# Teensylu2-0_9.net
KiCad netlist of a schematic drawn in EAGLE
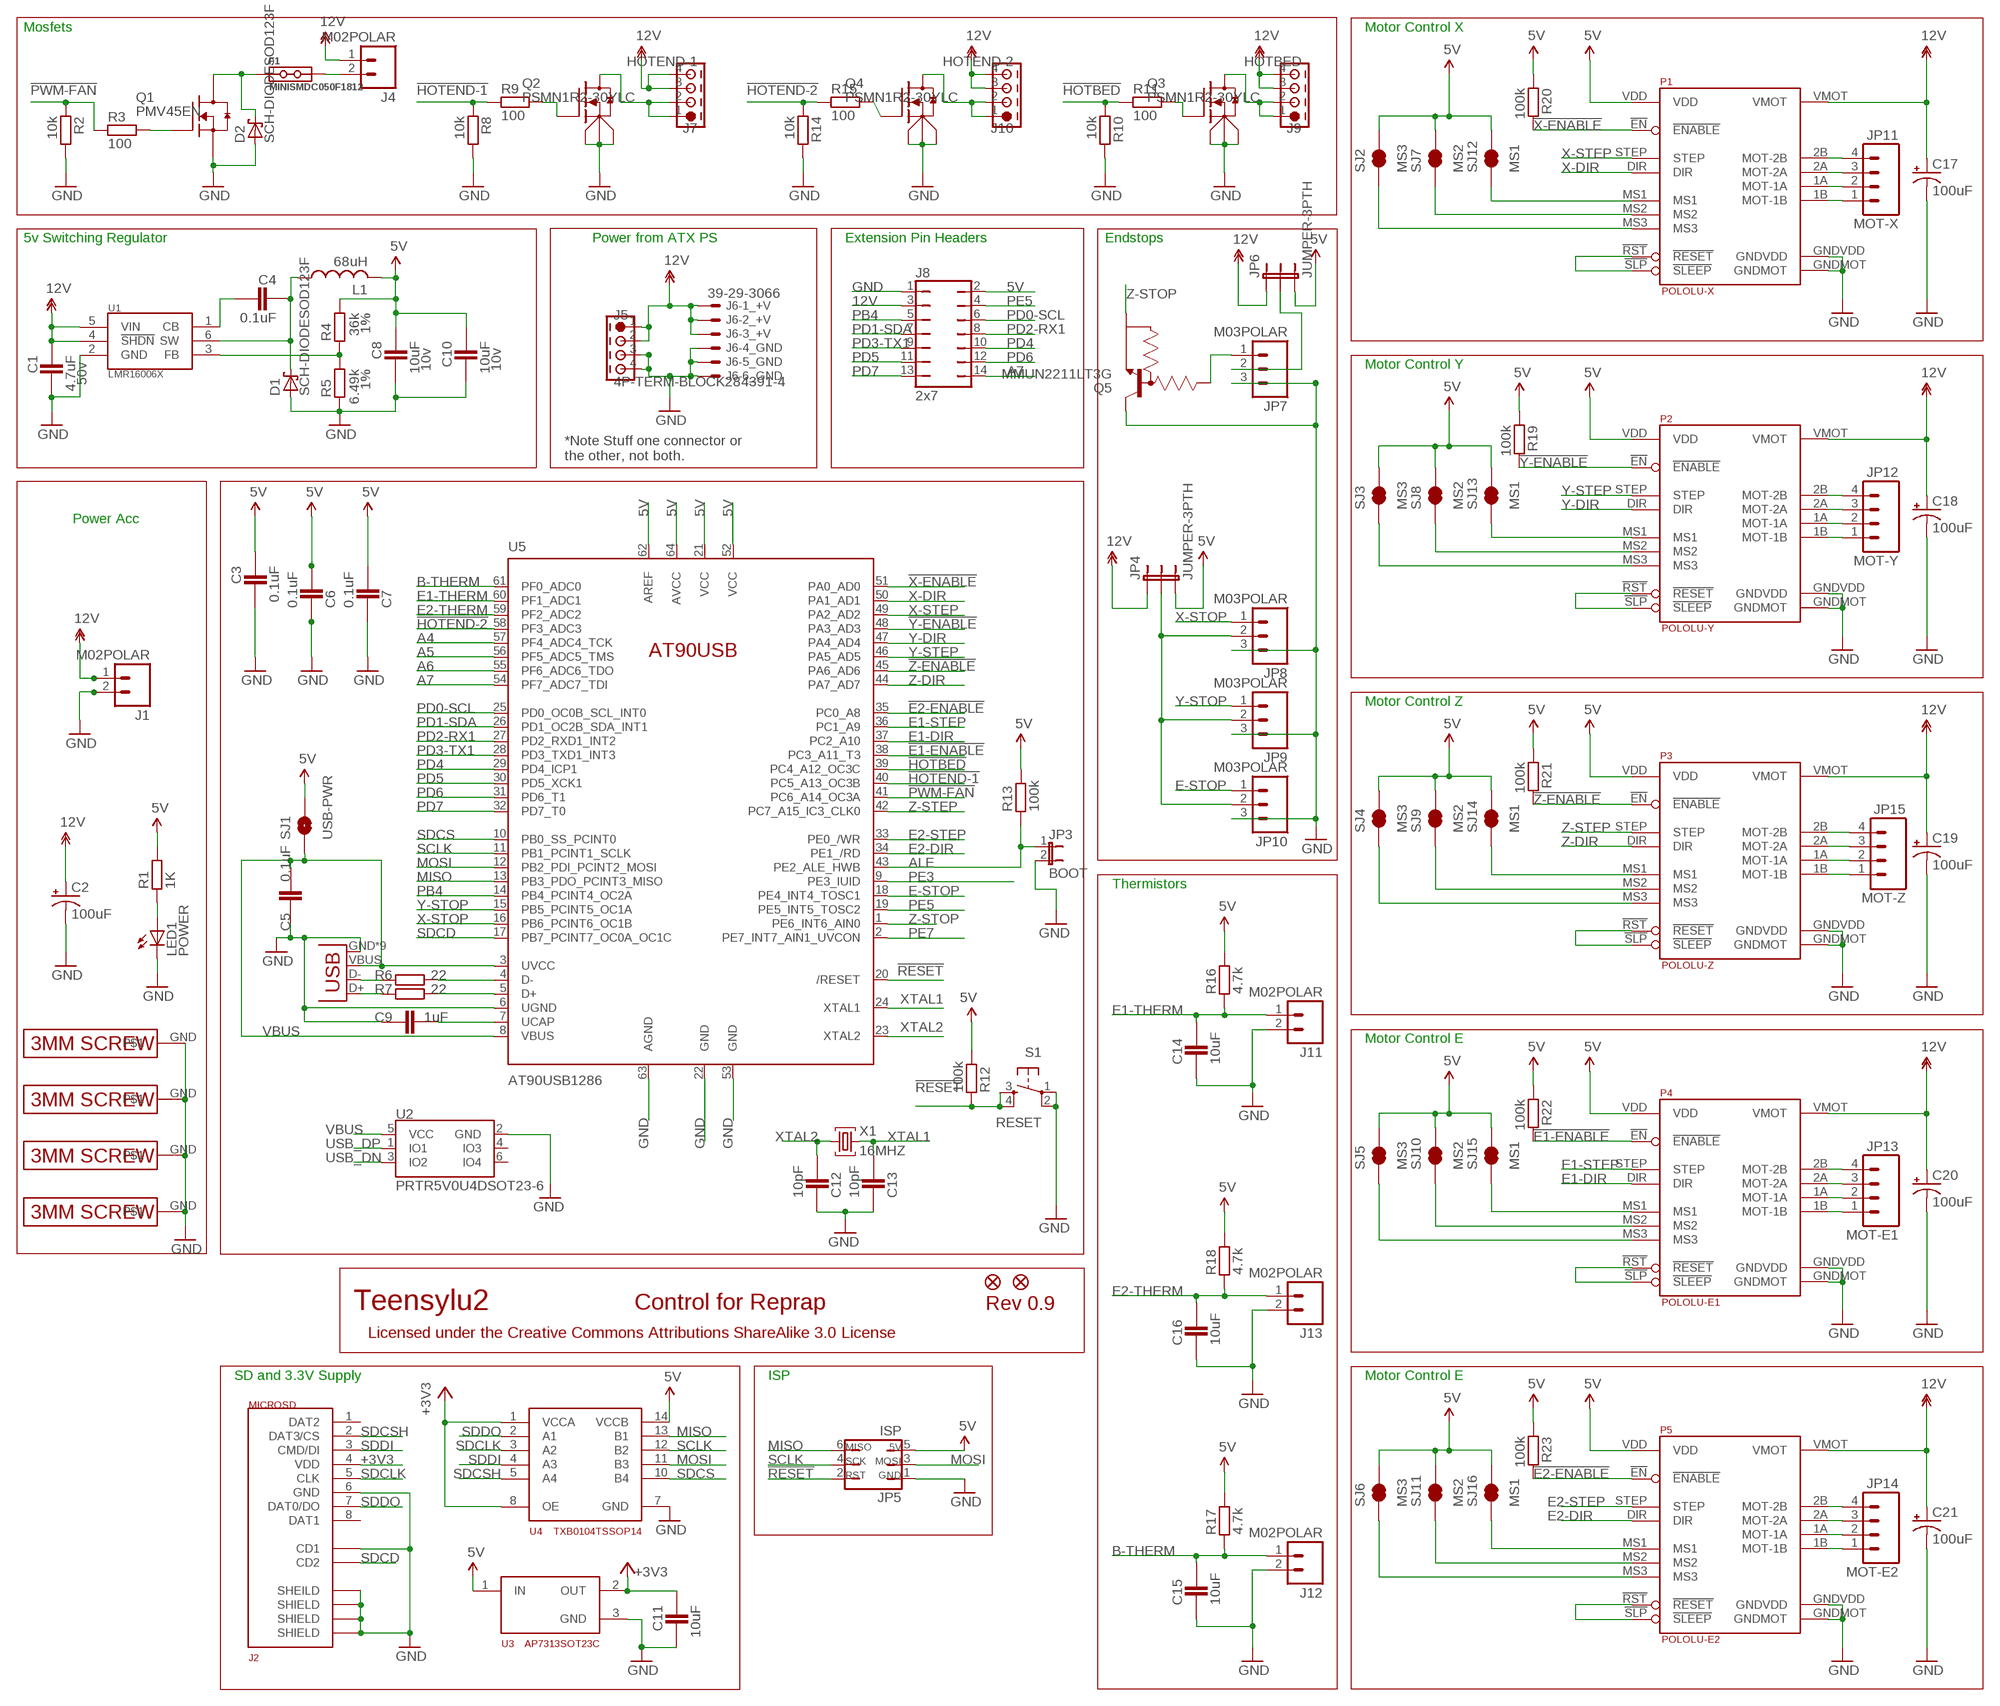
[diagram p0: schematic, sheet 1]

(export (version "E")
  (design (tool "Eeschema 10.0.6"))
  (components
    (comp (ref "C1")
      (value "4.7uF")
      (footprint "eagle-import:CAPC3215X168N")
      (fields
        (field (name "MANUFACTURER") "Yaiyo Yuden")
        (field (name "MANUFACTURER_PART_NUMBER") "UMK316AB7475KL-T")
        (field (name "TOLERANCE") "10%")
        (field (name "VDC") "50v")
      )
      (libsource (lib "eagle-import") (part "CAPACITOR_1206"))
    )
    (comp (ref "C2")
      (value "100uF")
      (footprint "eagle-import:PANASONIC_D")
      (fields
        (field (name "MANUFACTURER") "Panasonic")
        (field (name "MANUFACTURER_PART_NUMBER") "EEE-FTH101XAP")
        (field (name "TOLERANCE") "20%")
      )
      (libsource (lib "eagle-import") (part "CPOL-USD"))
    )
    (comp (ref "C3")
      (value "0.1uF")
      (footprint "eagle-import:CAPC1608X92N")
      (fields
        (field (name "MANUFACTURER") "Murata")
        (field (name "MANUFACTURER_PART_NUMBER") "GRM188R71C104KA01D")
        (field (name "TOLERANCE") "10%")
      )
      (libsource (lib "eagle-import") (part "CAPACITOR_0603"))
    )
    (comp (ref "C4")
      (value "0.1uF")
      (footprint "eagle-import:CAPC1608X92N")
      (fields
        (field (name "MANUFACTURER") "Samsung")
        (field (name "MANUFACTURER_PART_NUMBER") "CL10B104KB8NNNC")
        (field (name "TOLERANCE") "10%")
      )
      (libsource (lib "eagle-import") (part "CAPACITOR_0603"))
    )
    (comp (ref "C5")
      (value "0.1uF")
      (footprint "eagle-import:CAPC1608X92N")
      (fields
        (field (name "MANUFACTURER") "Murata")
        (field (name "MANUFACTURER_PART_NUMBER") "GRM188R71C104KA01D")
        (field (name "TOLERANCE") "10%")
      )
      (libsource (lib "eagle-import") (part "CAPACITOR_0603"))
    )
    (comp (ref "C6")
      (value "0.1uF")
      (footprint "eagle-import:CAPC1608X92N")
      (fields
        (field (name "MANUFACTURER") "Murata")
        (field (name "MANUFACTURER_PART_NUMBER") "GRM188R71C104KA01D")
        (field (name "TOLERANCE") "10%")
      )
      (libsource (lib "eagle-import") (part "CAPACITOR_0603"))
    )
    (comp (ref "C7")
      (value "0.1uF")
      (footprint "eagle-import:CAPC1608X92N")
      (fields
        (field (name "MANUFACTURER") "Murata")
        (field (name "MANUFACTURER_PART_NUMBER") "GRM188R71C104KA01D")
        (field (name "TOLERANCE") "10%")
      )
      (libsource (lib "eagle-import") (part "CAPACITOR_0603"))
    )
    (comp (ref "C8")
      (value "10uF")
      (footprint "eagle-import:CAPC2012X145AN")
      (fields
        (field (name "MANUFACTURER") "Murata")
        (field (name "MANUFACTURER_PART_NUMBER") "GRM21BR71A106KE51L")
        (field (name "TOLERANCE") "10%")
        (field (name "VDC") "10v")
      )
      (libsource (lib "eagle-import") (part "CAPACITOR_0805"))
    )
    (comp (ref "C9")
      (value "1uF")
      (footprint "eagle-import:CAPC1608X92N")
      (fields
        (field (name "MANUFACTURER") "Samsung")
        (field (name "MANUFACTURER_PART_NUMBER") "CL10A105MO8NNNC")
        (field (name "TOLERANCE") "20%")
      )
      (libsource (lib "eagle-import") (part "CAPACITOR_0603"))
    )
    (comp (ref "C10")
      (value "10uF")
      (footprint "eagle-import:CAPC2012X145AN")
      (fields
        (field (name "MANUFACTURER") "Murata")
        (field (name "MANUFACTURER_PART_NUMBER") "GRM21BR71A106KE51L")
        (field (name "TOLERANCE") "10%")
        (field (name "VDC") "10v")
      )
      (libsource (lib "eagle-import") (part "CAPACITOR_0805"))
    )
    (comp (ref "C11")
      (value "10uF")
      (footprint "eagle-import:CAPC1608X92N")
      (fields
        (field (name "MANUFACTURER") "Murata")
        (field (name "MANUFACTURER_PART_NUMBER") "GRM188R61C106MA73D")
        (field (name "TOLERANCE") "20%")
      )
      (libsource (lib "eagle-import") (part "CAPACITOR_0603"))
    )
    (comp (ref "C12")
      (value "10pF")
      (footprint "eagle-import:CAPC1608X92N")
      (fields
        (field (name "MANUFACTURER") "Samsung")
        (field (name "MANUFACTURER_PART_NUMBER") "CL10C100JB8NCNC")
        (field (name "TOLERANCE") "5%")
      )
      (libsource (lib "eagle-import") (part "CAPACITOR_0603"))
    )
    (comp (ref "C13")
      (value "10pF")
      (footprint "eagle-import:CAPC1608X92N")
      (fields
        (field (name "MANUFACTURER") "Samsung")
        (field (name "MANUFACTURER_PART_NUMBER") "CL10C100JB8NCNC")
        (field (name "TOLERANCE") "5%")
      )
      (libsource (lib "eagle-import") (part "CAPACITOR_0603"))
    )
    (comp (ref "C14")
      (value "10uF")
      (footprint "eagle-import:CAPC1608X92N")
      (fields
        (field (name "MANUFACTURER") "Murata")
        (field (name "MANUFACTURER_PART_NUMBER") "GRM188R61C106MA73D")
        (field (name "TOLERANCE") "20%")
      )
      (libsource (lib "eagle-import") (part "CAPACITOR_0603"))
    )
    (comp (ref "C15")
      (value "10uF")
      (footprint "eagle-import:CAPC1608X92N")
      (fields
        (field (name "MANUFACTURER") "Murata")
        (field (name "MANUFACTURER_PART_NUMBER") "GRM188R61C106MA73D")
        (field (name "TOLERANCE") "20%")
      )
      (libsource (lib "eagle-import") (part "CAPACITOR_0603"))
    )
    (comp (ref "C16")
      (value "10uF")
      (footprint "eagle-import:CAPC1608X92N")
      (fields
        (field (name "MANUFACTURER") "Murata")
        (field (name "MANUFACTURER_PART_NUMBER") "GRM188R61C106MA73D")
        (field (name "TOLERANCE") "20%")
      )
      (libsource (lib "eagle-import") (part "CAPACITOR_0603"))
    )
    (comp (ref "C17")
      (value "100uF")
      (footprint "eagle-import:PANASONIC_D")
      (fields
        (field (name "MANUFACTURER") "Panasonic")
        (field (name "MANUFACTURER_PART_NUMBER") "EEE-FTH101XAP")
        (field (name "TOLERANCE") "20%")
      )
      (libsource (lib "eagle-import") (part "CPOL-USD"))
    )
    (comp (ref "C18")
      (value "100uF")
      (footprint "eagle-import:PANASONIC_D")
      (fields
        (field (name "MANUFACTURER") "Panasonic")
        (field (name "MANUFACTURER_PART_NUMBER") "EEE-FTH101XAP")
        (field (name "TOLERANCE") "20%")
      )
      (libsource (lib "eagle-import") (part "CPOL-USD"))
    )
    (comp (ref "C19")
      (value "100uF")
      (footprint "eagle-import:PANASONIC_D")
      (fields
        (field (name "MANUFACTURER") "Panasonic")
        (field (name "MANUFACTURER_PART_NUMBER") "EEE-FTH101XAP")
        (field (name "TOLERANCE") "20%")
      )
      (libsource (lib "eagle-import") (part "CPOL-USD"))
    )
    (comp (ref "C20")
      (value "100uF")
      (footprint "eagle-import:PANASONIC_D")
      (fields
        (field (name "MANUFACTURER") "Panasonic")
        (field (name "MANUFACTURER_PART_NUMBER") "EEE-FTH101XAP")
        (field (name "TOLERANCE") "20%")
      )
      (libsource (lib "eagle-import") (part "CPOL-USD"))
    )
    (comp (ref "C21")
      (value "100uF")
      (footprint "eagle-import:PANASONIC_D")
      (fields
        (field (name "MANUFACTURER") "Panasonic")
        (field (name "MANUFACTURER_PART_NUMBER") "EEE-FTH101XAP")
        (field (name "TOLERANCE") "20%")
      )
      (libsource (lib "eagle-import") (part "CPOL-USD"))
    )
    (comp (ref "D1")
      (value "SCH-DIODESOD123F")
      (footprint "eagle-import:SOD123F")
      (fields
        (field (name "MANUFACTURER") "NXP Semiconductors")
        (field (name "MANUFACTURER_PART_NUMBER") "PMEG4010CEH,115")
        (field (name "CURRENT") "1A")
        (field (name "MANUFACTURER_1") "NXP Semiconductors")
        (field (name "MANUFACTURER_PART_NUMBER_1") "PMEG4010CEH,115")
        (field (name "REVERSE_VOLTAGE") "40V")
      )
      (libsource (lib "eagle-import") (part "SCH-DIODESOD123F"))
    )
    (comp (ref "D2")
      (value "SCH-DIODESOD123F")
      (footprint "eagle-import:SOD123F")
      (fields
        (field (name "MANUFACTURER") "NXP Semiconductors")
        (field (name "MANUFACTURER_PART_NUMBER") "PMEG4010CEH,115")
        (field (name "CURRENT") "1A")
        (field (name "MANUFACTURER_1") "NXP Semiconductors")
      )
      (libsource (lib "eagle-import") (part "SCH-DIODESOD123F"))
    )
    (comp (ref "F1")
      (value "MINISMDC050F1812")
      (footprint "eagle-import:MINISMDC")
      (fields
        (field (name "MANUFACTURER") "TE Connectivity")
        (field (name "MANUFACTURER_PART_NUMBER") "MINISMDC050F-2")
      )
      (libsource (lib "eagle-import") (part "MINISMDC050F1812"))
    )
    (comp (ref "J1")
      (value "M02POLAR")
      (footprint "eagle-import:MOLEX-1X2")
      (description "CONN HEADER 2POS .100 VERT TIN")
      (fields (field (name "MANUFACTURER") "Molex") (field (name "MANUFACTURER_PART_NUMBER") "0022272021"))
      (libsource (lib "eagle-import") (part "M02POLAR"))
    )
    (comp (ref "J2")
      (value "MICROSD")
      (footprint "eagle-import:AMPHENOL-MICROSD")
      (description "CONN MICRO SD CARD PUSH-PULL R/A")
      (fields
        (field (name "MANUFACTURER") "Amphenol")
        (field (name "MANUFACTURER_PART_NUMBER") "114-00841-68")
      )
      (libsource (lib "eagle-import") (part "MICROSD"))
    )
    (comp (ref "J3")
      (value "USB-MICRO-PTH")
      (footprint "eagle-import:USB-MICROB-PTH")
      (fields (field (name "MANUFACTURER") "FCI") (field (name "MANUFACTURER_PART_NUMBER") "10118194-0001LF"))
      (libsource (lib "eagle-import") (part "USB-MICRO-PTH"))
    )
    (comp (ref "J4")
      (value "M02POLAR")
      (footprint "eagle-import:MOLEX-1X2")
      (description "CONN HEADER 2POS .100 VERT TIN")
      (fields (field (name "MANUFACTURER") "Molex") (field (name "MANUFACTURER_PART_NUMBER") "0022272021"))
      (libsource (lib "eagle-import") (part "M02POLAR"))
    )
    (comp (ref "J5")
      (value "4P-TERM-BLOCK284391-4")
      (footprint "eagle-import:284391-4")
      (fields
        (field (name "MANUFACTURER") "TE Connectivity")
        (field (name "MANUFACTURER_PART_NUMBER") "284391-4")
      )
      (libsource (lib "eagle-import") (part "4P-TERM-BLOCK284391-4"))
    )
    (comp (ref "J6")
      (value "39-29-3066")
      (footprint "eagle-import:39-29-3066")
      (fields (field (name "MANUFACTURER") "Molex") (field (name "MANUFACTURER_PART_NUMBER") "0039293066"))
      (libsource (lib "eagle-import") (part "39-29-3066"))
    )
    (comp (ref "J7")
      (value "HOTEND-1")
      (footprint "eagle-import:282834-4")
      (fields
        (field (name "MANUFACTURER") "TE Connectivity")
        (field (name "MANUFACTURER_PART_NUMBER") "282834-4")
      )
      (libsource (lib "eagle-import") (part "4P-TERM-BLOCK282834-4"))
    )
    (comp (ref "J8")
      (value "2x7")
      (footprint "eagle-import:JP7Q")
      (description "DIL VERTICAL PC TAIL PIN HEADER")
      (fields (field (name "MANUFACTURER") "Harwin") (field (name "MANUFACTURER_PART_NUMBER") "M20-9980746"))
      (libsource (lib "eagle-import") (part "JP7Q"))
    )
    (comp (ref "J9")
      (value "HOTBED")
      (footprint "eagle-import:284391-4")
      (fields
        (field (name "MANUFACTURER") "TE Connectivity")
        (field (name "MANUFACTURER_PART_NUMBER") "284391-4")
      )
      (libsource (lib "eagle-import") (part "4P-TERM-BLOCK284391-4"))
    )
    (comp (ref "J10")
      (value "HOTEND-2")
      (footprint "eagle-import:282834-4")
      (fields
        (field (name "MANUFACTURER") "TE Connectivity")
        (field (name "MANUFACTURER_PART_NUMBER") "282834-4")
      )
      (libsource (lib "eagle-import") (part "4P-TERM-BLOCK282834-4"))
    )
    (comp (ref "J11")
      (value "M02POLAR")
      (footprint "eagle-import:MOLEX-1X2")
      (description "CONN HEADER 2POS .100 VERT TIN")
      (fields (field (name "MANUFACTURER") "Molex") (field (name "MANUFACTURER_PART_NUMBER") "0022272021"))
      (libsource (lib "eagle-import") (part "M02POLAR"))
    )
    (comp (ref "J12")
      (value "M02POLAR")
      (footprint "eagle-import:MOLEX-1X2")
      (description "CONN HEADER 2POS .100 VERT TIN")
      (fields (field (name "MANUFACTURER") "Molex") (field (name "MANUFACTURER_PART_NUMBER") "0022272021"))
      (libsource (lib "eagle-import") (part "M02POLAR"))
    )
    (comp (ref "J13")
      (value "M02POLAR")
      (footprint "eagle-import:MOLEX-1X2")
      (description "CONN HEADER 2POS .100 VERT TIN")
      (fields (field (name "MANUFACTURER") "Molex") (field (name "MANUFACTURER_PART_NUMBER") "0022272021"))
      (libsource (lib "eagle-import") (part "M02POLAR"))
    )
    (comp (ref "JP1")
      (value "FIDUCIAL1X2.5")
      (footprint "eagle-import:FIDUCIAL-1X2.5")
      (libsource (lib "eagle-import") (part "FIDUCIAL1X2.5"))
    )
    (comp (ref "JP2")
      (value "FIDUCIAL1X2.5")
      (footprint "eagle-import:FIDUCIAL-1X2.5")
      (libsource (lib "eagle-import") (part "FIDUCIAL1X2.5"))
    )
    (comp (ref "JP3")
      (value "BOOT")
      (footprint "eagle-import:1X02")
      (description "SIL VERTICAL PC TAIL PIN HEADER")
      (fields (field (name "MANUFACTURER") "Harwin") (field (name "MANUFACTURER_PART_NUMBER") "M20-9990246"))
      (libsource (lib "eagle-import") (part "JUMPER-2PTH"))
    )
    (comp (ref "JP4")
      (value "JUMPER-3PTH")
      (footprint "eagle-import:1X03")
      (libsource (lib "eagle-import") (part "JUMPER-3PTH"))
    )
    (comp (ref "JP5")
      (value "ISP")
      (footprint "eagle-import:ISP")
      (libsource (lib "eagle-import") (part "PROGHEADER"))
    )
    (comp (ref "JP6")
      (value "JUMPER-3PTH")
      (footprint "eagle-import:1X03")
      (libsource (lib "eagle-import") (part "JUMPER-3PTH"))
    )
    (comp (ref "JP7")
      (value "M03POLAR")
      (footprint "eagle-import:MOLEX-1X3")
      (description "CONN HEADER 3POS .100 VERT TIN")
      (fields (field (name "MANUFACTURER") "Molex") (field (name "MANUFACTURER_PART_NUMBER") "0022272031"))
      (libsource (lib "eagle-import") (part "M03POLAR"))
    )
    (comp (ref "JP8")
      (value "M03POLAR")
      (footprint "eagle-import:MOLEX-1X3")
      (description "CONN HEADER 3POS .100 VERT TIN")
      (fields (field (name "MANUFACTURER") "Molex") (field (name "MANUFACTURER_PART_NUMBER") "0022272031"))
      (libsource (lib "eagle-import") (part "M03POLAR"))
    )
    (comp (ref "JP9")
      (value "M03POLAR")
      (footprint "eagle-import:MOLEX-1X3")
      (description "CONN HEADER 3POS .100 VERT TIN")
      (fields (field (name "MANUFACTURER") "Molex") (field (name "MANUFACTURER_PART_NUMBER") "0022272031"))
      (libsource (lib "eagle-import") (part "M03POLAR"))
    )
    (comp (ref "JP10")
      (value "M03POLAR")
      (footprint "eagle-import:MOLEX-1X3")
      (description "CONN HEADER 3POS .100 VERT TIN")
      (fields (field (name "MANUFACTURER") "Molex") (field (name "MANUFACTURER_PART_NUMBER") "0022272031"))
      (libsource (lib "eagle-import") (part "M03POLAR"))
    )
    (comp (ref "JP11")
      (value "MOT-X")
      (footprint "eagle-import:MOLEX-1X4")
      (fields (field (name "MANUFACTURER") "Molex") (field (name "MANUFACTURER_PART_NUMBER") "0022272041"))
      (libsource (lib "eagle-import") (part "M04POLAR"))
    )
    (comp (ref "JP12")
      (value "MOT-Y")
      (footprint "eagle-import:MOLEX-1X4")
      (fields (field (name "MANUFACTURER") "Molex") (field (name "MANUFACTURER_PART_NUMBER") "0022272041"))
      (libsource (lib "eagle-import") (part "M04POLAR"))
    )
    (comp (ref "JP13")
      (value "MOT-E1")
      (footprint "eagle-import:MOLEX-1X4")
      (fields (field (name "MANUFACTURER") "Molex") (field (name "MANUFACTURER_PART_NUMBER") "0022272041"))
      (libsource (lib "eagle-import") (part "M04POLAR"))
    )
    (comp (ref "JP14")
      (value "MOT-E2")
      (footprint "eagle-import:MOLEX-1X4")
      (fields (field (name "MANUFACTURER") "Molex") (field (name "MANUFACTURER_PART_NUMBER") "0022272041"))
      (libsource (lib "eagle-import") (part "M04POLAR"))
    )
    (comp (ref "JP15")
      (value "MOT-Z")
      (footprint "eagle-import:MOLEX-1X4")
      (fields (field (name "MANUFACTURER") "Molex") (field (name "MANUFACTURER_PART_NUMBER") "0022272041"))
      (libsource (lib "eagle-import") (part "M04POLAR"))
    )
    (comp (ref "L1")
      (value "68uH")
      (footprint "eagle-import:SRN6045")
      (fields
        (field (name "MANUFACTURER") "Bourns")
        (field (name "MANUFACTURER_PART_NUMBER") "SRN6045-680M")
        (field (name "MANUFACTURER_1") "Bourns")
        (field (name "MANUFACTURER_PART_NUMBER_1") "SRN6045-680M")
      )
      (libsource (lib "eagle-import") (part "INDUCTORSRN6045"))
    )
    (comp (ref "LED1")
      (value "POWER")
      (footprint "eagle-import:CHIPLED_0805")
      (fields
        (field (name "MANUFACTURER") "Kingbright")
        (field (name "MANUFACTURER_PART_NUMBER") "APT2012SGC")
      )
      (libsource (lib "eagle-import") (part "LEDCHIPLED_0805"))
    )
    (comp (ref "P1")
      (value "POLOLU-X")
      (footprint "eagle-import:POLOLU-STEPPER-PTH")
      (libsource (lib "eagle-import") (part "POLOLU-ALLEGRO"))
    )
    (comp (ref "P2")
      (value "POLOLU-Y")
      (footprint "eagle-import:POLOLU-STEPPER-PTH")
      (libsource (lib "eagle-import") (part "POLOLU-ALLEGRO"))
    )
    (comp (ref "P3")
      (value "POLOLU-Z")
      (footprint "eagle-import:POLOLU-STEPPER-PTH")
      (libsource (lib "eagle-import") (part "POLOLU-ALLEGRO"))
    )
    (comp (ref "P4")
      (value "POLOLU-E1")
      (footprint "eagle-import:POLOLU-STEPPER-PTH")
      (libsource (lib "eagle-import") (part "POLOLU-ALLEGRO"))
    )
    (comp (ref "P5")
      (value "POLOLU-E2")
      (footprint "eagle-import:POLOLU-STEPPER-PTH")
      (libsource (lib "eagle-import") (part "POLOLU-ALLEGRO"))
    )
    (comp (ref "Q1")
      (value "PMV45EN")
      (footprint "eagle-import:SOT23C")
      (fields
        (field (name "MANUFACTURER") "International Rectifier")
        (field (name "MANUFACTURER_PART_NUMBER") "IRLML2060TRPBF")
        (field (name "VOLTAGE") "60V")
      )
      (libsource (lib "eagle-import") (part "MOSFET-NCH_SOT-23"))
    )
    (comp (ref "Q2")
      (value "PSMN1R2-30YLC")
      (footprint "eagle-import:LFPACK-POWERPAK-SO8")
      (fields
        (field (name "MANUFACTURER") "NXP Semiconductors")
        (field (name "MANUFACTURER_PART_NUMBER") "PSMN1R2-30YLC,115")
        (field (name "VOLTAGE") "30V")
      )
      (libsource (lib "eagle-import") (part "PSMN1R2-30YLCPOWERPACK-S08"))
    )
    (comp (ref "Q3")
      (value "PSMN1R2-30YLC")
      (footprint "eagle-import:LFPACK-POWERPAK-SO8")
      (fields
        (field (name "MANUFACTURER") "NXP Semiconductors")
        (field (name "MANUFACTURER_PART_NUMBER") "PSMN1R2-30YLC,115")
        (field (name "VOLTAGE") "30V")
      )
      (libsource (lib "eagle-import") (part "PSMN1R2-30YLCPOWERPACK-S08"))
    )
    (comp (ref "Q4")
      (value "PSMN1R2-30YLC")
      (footprint "eagle-import:LFPACK-POWERPAK-SO8")
      (fields
        (field (name "MANUFACTURER") "NXP Semiconductors")
        (field (name "MANUFACTURER_PART_NUMBER") "PSMN1R2-30YLC,115")
        (field (name "VOLTAGE") "30V")
      )
      (libsource (lib "eagle-import") (part "PSMN1R2-30YLCPOWERPACK-S08"))
    )
    (comp (ref "Q5")
      (value "MMUN2211LT3G")
      (footprint "eagle-import:SOT23C")
      (description "TRANS PREBIAS NPN 246MW SOT23-3")
      (fields (field (name "MANUFACTURER") "ON Semiconductor"))
      (libsource (lib "eagle-import") (part "TRANSISTOR_NPN_BIASSOT23C"))
    )
    (comp (ref "R1")
      (value "1K")
      (footprint "eagle-import:RESC1608X55N")
      (libsource (lib "eagle-import") (part "RESISTOR_0603"))
    )
    (comp (ref "R2")
      (value "10k")
      (footprint "eagle-import:RESC1608X55N")
      (libsource (lib "eagle-import") (part "RESISTOR_0603"))
    )
    (comp (ref "R3")
      (value "100")
      (footprint "eagle-import:RESC1608X55N")
      (libsource (lib "eagle-import") (part "RESISTOR_0603"))
    )
    (comp (ref "R4")
      (value "36k")
      (footprint "eagle-import:RESC1608X55N")
      (fields (field (name "TOLERANCE") "1%"))
      (libsource (lib "eagle-import") (part "RESISTOR_0603"))
    )
    (comp (ref "R5")
      (value "6.49k")
      (footprint "eagle-import:RESC1608X55N")
      (fields (field (name "TOLERANCE") "1%"))
      (libsource (lib "eagle-import") (part "RESISTOR_0603"))
    )
    (comp (ref "R6")
      (value "22")
      (footprint "eagle-import:RESC1608X55N")
      (libsource (lib "eagle-import") (part "RESISTOR_0603"))
    )
    (comp (ref "R7")
      (value "22")
      (footprint "eagle-import:RESC1608X55N")
      (libsource (lib "eagle-import") (part "RESISTOR_0603"))
    )
    (comp (ref "R8")
      (value "10k")
      (footprint "eagle-import:RESC1608X55N")
      (libsource (lib "eagle-import") (part "RESISTOR_0603"))
    )
    (comp (ref "R9")
      (value "100")
      (footprint "eagle-import:RESC1608X55N")
      (libsource (lib "eagle-import") (part "RESISTOR_0603"))
    )
    (comp (ref "R10")
      (value "10k")
      (footprint "eagle-import:RESC1608X55N")
      (libsource (lib "eagle-import") (part "RESISTOR_0603"))
    )
    (comp (ref "R11")
      (value "100")
      (footprint "eagle-import:RESC1608X55N")
      (libsource (lib "eagle-import") (part "RESISTOR_0603"))
    )
    (comp (ref "R12")
      (value "100k")
      (footprint "eagle-import:RESC1608X55N")
      (libsource (lib "eagle-import") (part "RESISTOR_0603"))
    )
    (comp (ref "R13")
      (value "100k")
      (footprint "eagle-import:RESC1608X55N")
      (libsource (lib "eagle-import") (part "RESISTOR_0603"))
    )
    (comp (ref "R14")
      (value "10k")
      (footprint "eagle-import:RESC1608X55N")
      (libsource (lib "eagle-import") (part "RESISTOR_0603"))
    )
    (comp (ref "R15")
      (value "100")
      (footprint "eagle-import:RESC1608X55N")
      (libsource (lib "eagle-import") (part "RESISTOR_0603"))
    )
    (comp (ref "R16")
      (value "4.7k")
      (footprint "eagle-import:RESC1608X55N")
      (libsource (lib "eagle-import") (part "RESISTOR_0603"))
    )
    (comp (ref "R17")
      (value "4.7k")
      (footprint "eagle-import:RESC1608X55N")
      (libsource (lib "eagle-import") (part "RESISTOR_0603"))
    )
    (comp (ref "R18")
      (value "4.7k")
      (footprint "eagle-import:RESC1608X55N")
      (libsource (lib "eagle-import") (part "RESISTOR_0603"))
    )
    (comp (ref "R19")
      (value "100k")
      (footprint "eagle-import:RESC1608X55N")
      (libsource (lib "eagle-import") (part "RESISTOR_0603"))
    )
    (comp (ref "R20")
      (value "100k")
      (footprint "eagle-import:RESC1608X55N")
      (libsource (lib "eagle-import") (part "RESISTOR_0603"))
    )
    (comp (ref "R21")
      (value "100k")
      (footprint "eagle-import:RESC1608X55N")
      (libsource (lib "eagle-import") (part "RESISTOR_0603"))
    )
    (comp (ref "R22")
      (value "100k")
      (footprint "eagle-import:RESC1608X55N")
      (libsource (lib "eagle-import") (part "RESISTOR_0603"))
    )
    (comp (ref "R23")
      (value "100k")
      (footprint "eagle-import:RESC1608X55N")
      (libsource (lib "eagle-import") (part "RESISTOR_0603"))
    )
    (comp (ref "S1")
      (value "RESET")
      (footprint "eagle-import:TACTILE_SWITCH_SMD")
      (fields (field (name "MANUFACTURER") "Bourns") (field (name "MANUFACTURER_PART_NUMBER") "7914J-1-000E"))
      (libsource (lib "eagle-import") (part "TAC_SWITCHSMD"))
    )
    (comp (ref "SCREW1")
      (value "3MM-SCREW")
      (footprint "eagle-import:PLATEDSCREW")
      (libsource (lib "eagle-import") (part "3MM-SCREW"))
    )
    (comp (ref "SCREW2")
      (value "3MM-SCREW")
      (footprint "eagle-import:PLATEDSCREW")
      (libsource (lib "eagle-import") (part "3MM-SCREW"))
    )
    (comp (ref "SCREW3")
      (value "3MM-SCREW")
      (footprint "eagle-import:PLATEDSCREW")
      (libsource (lib "eagle-import") (part "3MM-SCREW"))
    )
    (comp (ref "SCREW4")
      (value "3MM-SCREW")
      (footprint "eagle-import:PLATEDSCREW")
      (libsource (lib "eagle-import") (part "3MM-SCREW"))
    )
    (comp (ref "SJ1")
      (value "USB-PWR")
      (footprint "eagle-import:SJ_2S-NO")
      (libsource (lib "eagle-import") (part "SOLDERJUMPERNO"))
    )
    (comp (ref "SJ2")
      (value "MS3")
      (footprint "eagle-import:SJ_2S-TRACE")
      (libsource (lib "eagle-import") (part "SOLDERJUMPER-NCSJ-TRACE"))
    )
    (comp (ref "SJ3")
      (value "MS3")
      (footprint "eagle-import:SJ_2S-TRACE")
      (libsource (lib "eagle-import") (part "SOLDERJUMPER-NCSJ-TRACE"))
    )
    (comp (ref "SJ4")
      (value "MS3")
      (footprint "eagle-import:SJ_2S-TRACE")
      (libsource (lib "eagle-import") (part "SOLDERJUMPER-NCSJ-TRACE"))
    )
    (comp (ref "SJ5")
      (value "MS3")
      (footprint "eagle-import:SJ_2S-TRACE")
      (libsource (lib "eagle-import") (part "SOLDERJUMPER-NCSJ-TRACE"))
    )
    (comp (ref "SJ6")
      (value "MS3")
      (footprint "eagle-import:SJ_2S-TRACE")
      (libsource (lib "eagle-import") (part "SOLDERJUMPER-NCSJ-TRACE"))
    )
    (comp (ref "SJ7")
      (value "MS2")
      (footprint "eagle-import:SJ_2S-TRACE")
      (libsource (lib "eagle-import") (part "SOLDERJUMPER-NCSJ-TRACE"))
    )
    (comp (ref "SJ8")
      (value "MS2")
      (footprint "eagle-import:SJ_2S-TRACE")
      (libsource (lib "eagle-import") (part "SOLDERJUMPER-NCSJ-TRACE"))
    )
    (comp (ref "SJ9")
      (value "MS2")
      (footprint "eagle-import:SJ_2S-TRACE")
      (libsource (lib "eagle-import") (part "SOLDERJUMPER-NCSJ-TRACE"))
    )
    (comp (ref "SJ10")
      (value "MS2")
      (footprint "eagle-import:SJ_2S-TRACE")
      (libsource (lib "eagle-import") (part "SOLDERJUMPER-NCSJ-TRACE"))
    )
    (comp (ref "SJ11")
      (value "MS2")
      (footprint "eagle-import:SJ_2S-TRACE")
      (libsource (lib "eagle-import") (part "SOLDERJUMPER-NCSJ-TRACE"))
    )
    (comp (ref "SJ12")
      (value "MS1")
      (footprint "eagle-import:SJ_2S-TRACE")
      (libsource (lib "eagle-import") (part "SOLDERJUMPER-NCSJ-TRACE"))
    )
    (comp (ref "SJ13")
      (value "MS1")
      (footprint "eagle-import:SJ_2S-TRACE")
      (libsource (lib "eagle-import") (part "SOLDERJUMPER-NCSJ-TRACE"))
    )
    (comp (ref "SJ14")
      (value "MS1")
      (footprint "eagle-import:SJ_2S-TRACE")
      (libsource (lib "eagle-import") (part "SOLDERJUMPER-NCSJ-TRACE"))
    )
    (comp (ref "SJ15")
      (value "MS1")
      (footprint "eagle-import:SJ_2S-TRACE")
      (libsource (lib "eagle-import") (part "SOLDERJUMPER-NCSJ-TRACE"))
    )
    (comp (ref "SJ16")
      (value "MS1")
      (footprint "eagle-import:SJ_2S-TRACE")
      (libsource (lib "eagle-import") (part "SOLDERJUMPER-NCSJ-TRACE"))
    )
    (comp (ref "U1")
      (value "LMR16006X")
      (footprint "eagle-import:TSOT6")
      (fields
        (field (name "MANUFACTURER") "Texas Instruments")
        (field (name "MANUFACTURER_PART_NUMBER") "LMR16006XDDCT")
      )
      (libsource (lib "eagle-import") (part "LMR16006X"))
    )
    (comp (ref "U2")
      (value "PRTR5V0U4DSOT23-6")
      (footprint "eagle-import:SOT23-6")
      (fields
        (field (name "MANUFACTURER") "NXP Semiconductors")
        (field (name "MANUFACTURER_PART_NUMBER") "PRTR5V0U4D,125")
      )
      (libsource (lib "eagle-import") (part "PRTR5V0U4DSOT23-6"))
    )
    (comp (ref "U3")
      (value "AP7313SOT23C")
      (footprint "eagle-import:SOT23C")
      (description "IC REG LDO 3.3V 0.15A SOT23-3")
      (fields
        (field (name "MANUFACTURER") "Diodes Incorporated")
        (field (name "MANUFACTURER_PART_NUMBER") "AP7313-33SAG-7")
      )
      (libsource (lib "eagle-import") (part "AP7313SOT23C"))
    )
    (comp (ref "U4")
      (value "TXB0104TSSOP14")
      (footprint "eagle-import:TSSOP14")
      (description "IC VOLT-LEVEL TRANSLATOR 14TSSOP")
      (fields
        (field (name "MANUFACTURER") "Texas Instruments")
        (field (name "MANUFACTURER_PART_NUMBER") "TXB0104PWR")
      )
      (libsource (lib "eagle-import") (part "TXB0104TSSOP14"))
    )
    (comp (ref "U5")
      (value "AT90USB1286")
      (footprint "eagle-import:TQFP64-2")
      (fields (field (name "MANUFACTURER") "Atmel"))
      (libsource (lib "eagle-import") (part "AT90USB"))
    )
    (comp (ref "X1")
      (value "16MHZ")
      (footprint "eagle-import:NDK-XTAL")
      (fields
        (field (name "MANUFACTURER") "NDK")
        (field (name "MANUFACTURER_PART_NUMBER") "NX5032GA-16.000000MHZ-LN-CD-1")
      )
      (libsource (lib "eagle-import") (part "XTAL"))
    )
  )
  (nets
    (net (code "1") (name "+3V3") (class "Default")
      (node (ref "C11") (pin "1") (pinfunction "1_1") (pintype "passive"))
      (node (ref "J2") (pin "4") (pinfunction "VDD_4") (pintype "power_in"))
      (node (ref "U3") (pin "2") (pinfunction "OUT_2") (pintype "power_in"))
      (node (ref "U4") (pin "1") (pinfunction "VCCA_1") (pintype "power_in"))
      (node (ref "U4") (pin "8") (pinfunction "OE_8") (pintype "input"))
    )
    (net (code "2") (name "/A4") (class "Default")
      (node (ref "U5") (pin "57") (pinfunction "PF4_ADC4_TCK_57") (pintype "bidirectional"))
    )
    (net (code "3") (name "/A5") (class "Default")
      (node (ref "U5") (pin "56") (pinfunction "PF5_ADC5_TMS_56") (pintype "bidirectional"))
    )
    (net (code "4") (name "/A6") (class "Default")
      (node (ref "U5") (pin "55") (pinfunction "PF6_ADC6_TDO_55") (pintype "bidirectional"))
    )
    (net (code "5") (name "/A7") (class "Default")
      (node (ref "J8") (pin "14") (pinfunction "14_14") (pintype "passive"))
      (node (ref "U5") (pin "54") (pinfunction "PF7_ADC7_TDI_54") (pintype "bidirectional"))
    )
    (net (code "6") (name "/ALE") (class "Default")
      (node (ref "JP3") (pin "1") (pinfunction "1_1") (pintype "passive"))
      (node (ref "R13") (pin "1") (pinfunction "1_1") (pintype "passive"))
      (node (ref "U5") (pin "43") (pinfunction "PE2_ALE_HWB_43") (pintype "bidirectional"))
    )
    (net (code "7") (name "/B-THERM") (class "Default")
      (node (ref "C15") (pin "2") (pinfunction "2_2") (pintype "passive"))
      (node (ref "J12") (pin "1") (pinfunction "1_1") (pintype "passive"))
      (node (ref "R17") (pin "1") (pinfunction "1_1") (pintype "passive"))
      (node (ref "U5") (pin "61") (pinfunction "PF0_ADC0_61") (pintype "bidirectional"))
    )
    (net (code "8") (name "/E-STOP") (class "Default")
      (node (ref "JP10") (pin "1") (pinfunction "1_1") (pintype "passive"))
      (node (ref "U5") (pin "18") (pinfunction "PE4_INT4_TOSC1_18") (pintype "bidirectional"))
    )
    (net (code "9") (name "/E1-DIR") (class "Default")
      (node (ref "P4") (pin "DIR") (pinfunction "DIR_DIR") (pintype "bidirectional"))
      (node (ref "U5") (pin "37") (pinfunction "PC2_A10_37") (pintype "bidirectional"))
    )
    (net (code "10") (name "/E1-STEP") (class "Default")
      (node (ref "P4") (pin "STEP") (pinfunction "STEP_STEP") (pintype "bidirectional"))
      (node (ref "U5") (pin "36") (pinfunction "PC1_A9_36") (pintype "bidirectional"))
    )
    (net (code "11") (name "/E1-THERM") (class "Default")
      (node (ref "C14") (pin "2") (pinfunction "2_2") (pintype "passive"))
      (node (ref "J11") (pin "1") (pinfunction "1_1") (pintype "passive"))
      (node (ref "R16") (pin "1") (pinfunction "1_1") (pintype "passive"))
      (node (ref "U5") (pin "60") (pinfunction "PF1_ADC1_60") (pintype "bidirectional"))
    )
    (net (code "12") (name "/E2-DIR") (class "Default")
      (node (ref "P5") (pin "DIR") (pinfunction "DIR_DIR") (pintype "bidirectional"))
      (node (ref "U5") (pin "34") (pinfunction "PE1_/RD_34") (pintype "bidirectional"))
    )
    (net (code "13") (name "/E2-STEP") (class "Default")
      (node (ref "P5") (pin "STEP") (pinfunction "STEP_STEP") (pintype "bidirectional"))
      (node (ref "U5") (pin "33") (pinfunction "PE0_/WR_33") (pintype "bidirectional"))
    )
    (net (code "14") (name "/E2-THERM") (class "Default")
      (node (ref "C16") (pin "2") (pinfunction "2_2") (pintype "passive"))
      (node (ref "J13") (pin "1") (pinfunction "1_1") (pintype "passive"))
      (node (ref "R18") (pin "1") (pinfunction "1_1") (pintype "passive"))
      (node (ref "U5") (pin "59") (pinfunction "PF2_ADC2_59") (pintype "bidirectional"))
    )
    (net (code "15") (name "/MISO") (class "Default")
      (node (ref "JP5") (pin "6") (pinfunction "6_6") (pintype "passive"))
      (node (ref "U4") (pin "13") (pinfunction "B1_13") (pintype "bidirectional"))
      (node (ref "U5") (pin "13") (pinfunction "PB3_PDO_PCINT3_MISO_13") (pintype "bidirectional"))
    )
    (net (code "16") (name "/MOSI") (class "Default")
      (node (ref "JP5") (pin "3") (pinfunction "3_3") (pintype "passive"))
      (node (ref "U4") (pin "11") (pinfunction "B3_11") (pintype "bidirectional"))
      (node (ref "U5") (pin "12") (pinfunction "PB2_PDI_PCINT2_MOSI_12") (pintype "bidirectional"))
    )
    (net (code "17") (name "/PB4") (class "Default")
      (node (ref "J8") (pin "5") (pinfunction "5_5") (pintype "passive"))
      (node (ref "U5") (pin "14") (pinfunction "PB4_PCINT4_OC2A_14") (pintype "bidirectional"))
    )
    (net (code "18") (name "/PD0-SCL") (class "Default")
      (node (ref "J8") (pin "6") (pinfunction "6_6") (pintype "passive"))
      (node (ref "U5") (pin "25") (pinfunction "PD0_OC0B_SCL_INT0_25") (pintype "bidirectional"))
    )
    (net (code "19") (name "/PD1-SDA") (class "Default")
      (node (ref "J8") (pin "7") (pinfunction "7_7") (pintype "passive"))
      (node (ref "U5") (pin "26") (pinfunction "PD1_OC2B_SDA_INT1_26") (pintype "bidirectional"))
    )
    (net (code "20") (name "/PD2-RX1") (class "Default")
      (node (ref "J8") (pin "8") (pinfunction "8_8") (pintype "passive"))
      (node (ref "U5") (pin "27") (pinfunction "PD2_RXD1_INT2_27") (pintype "bidirectional"))
    )
    (net (code "21") (name "/PD3-TX1") (class "Default")
      (node (ref "J8") (pin "9") (pinfunction "9_9") (pintype "passive"))
      (node (ref "U5") (pin "28") (pinfunction "PD3_TXD1_INT3_28") (pintype "bidirectional"))
    )
    (net (code "22") (name "/PD4") (class "Default")
      (node (ref "J8") (pin "10") (pinfunction "10_10") (pintype "passive"))
      (node (ref "U5") (pin "29") (pinfunction "PD4_ICP1_29") (pintype "bidirectional"))
    )
    (net (code "23") (name "/PD5") (class "Default")
      (node (ref "J8") (pin "11") (pinfunction "11_11") (pintype "passive"))
      (node (ref "U5") (pin "30") (pinfunction "PD5_XCK1_30") (pintype "bidirectional"))
    )
    (net (code "24") (name "/PD6") (class "Default")
      (node (ref "J8") (pin "12") (pinfunction "12_12") (pintype "passive"))
      (node (ref "U5") (pin "31") (pinfunction "PD6_T1_31") (pintype "bidirectional"))
    )
    (net (code "25") (name "/PD7") (class "Default")
      (node (ref "J8") (pin "13") (pinfunction "13_13") (pintype "passive"))
      (node (ref "U5") (pin "32") (pinfunction "PD7_T0_32") (pintype "bidirectional"))
    )
    (net (code "26") (name "/PE3") (class "Default")
      (node (ref "U5") (pin "9") (pinfunction "PE3_IUID_9") (pintype "bidirectional"))
    )
    (net (code "27") (name "/PE5") (class "Default")
      (node (ref "J8") (pin "4") (pinfunction "4_4") (pintype "passive"))
      (node (ref "U5") (pin "19") (pinfunction "PE5_INT5_TOSC2_19") (pintype "bidirectional"))
    )
    (net (code "28") (name "/PE7") (class "Default")
      (node (ref "U5") (pin "2") (pinfunction "PE7_INT7_AIN1_UVCON_2") (pintype "bidirectional"))
    )
    (net (code "29") (name "/SCLK") (class "Default")
      (node (ref "JP5") (pin "4") (pinfunction "4_4") (pintype "passive"))
      (node (ref "U4") (pin "12") (pinfunction "B2_12") (pintype "bidirectional"))
      (node (ref "U5") (pin "11") (pinfunction "PB1_PCINT1_SCLK_11") (pintype "bidirectional"))
    )
    (net (code "30") (name "/SDCD") (class "Default")
      (node (ref "J2") (pin "CD2") (pinfunction "CD2_CD2") (pintype "bidirectional"))
      (node (ref "U5") (pin "17") (pinfunction "PB7_PCINT7_OC0A_OC1C_17") (pintype "bidirectional"))
    )
    (net (code "31") (name "/SDCLK") (class "Default")
      (node (ref "J2") (pin "5") (pinfunction "CLK_5") (pintype "input"))
      (node (ref "U4") (pin "3") (pinfunction "A2_3") (pintype "bidirectional"))
    )
    (net (code "32") (name "/SDCS") (class "Default")
      (node (ref "U4") (pin "10") (pinfunction "B4_10") (pintype "bidirectional"))
      (node (ref "U5") (pin "10") (pinfunction "PB0_SS_PCINT0_10") (pintype "bidirectional"))
    )
    (net (code "33") (name "/SDCSH") (class "Default")
      (node (ref "J2") (pin "2") (pinfunction "DAT3/CS_2") (pintype "bidirectional"))
      (node (ref "U4") (pin "5") (pinfunction "A4_5") (pintype "bidirectional"))
    )
    (net (code "34") (name "/SDDI") (class "Default")
      (node (ref "J2") (pin "3") (pinfunction "CMD/DI_3") (pintype "input"))
      (node (ref "U4") (pin "4") (pinfunction "A3_4") (pintype "bidirectional"))
    )
    (net (code "35") (name "/SDDO") (class "Default")
      (node (ref "J2") (pin "7") (pinfunction "DAT0/DO_7") (pintype "bidirectional"))
      (node (ref "U4") (pin "2") (pinfunction "A1_2") (pintype "bidirectional"))
    )
    (net (code "36") (name "/USB_DN") (class "Default")
      (node (ref "J3") (pin "D-") (pinfunction "D-_D-") (pintype "bidirectional"))
      (node (ref "R6") (pin "1") (pinfunction "1_1") (pintype "passive"))
      (node (ref "U2") (pin "3") (pinfunction "IO2_3") (pintype "bidirectional"))
    )
    (net (code "37") (name "/USB_DP") (class "Default")
      (node (ref "J3") (pin "D+") (pinfunction "D+_D+") (pintype "bidirectional"))
      (node (ref "R7") (pin "1") (pinfunction "1_1") (pintype "passive"))
      (node (ref "U2") (pin "1") (pinfunction "IO1_1") (pintype "bidirectional"))
    )
    (net (code "38") (name "/VBUS") (class "Default")
      (node (ref "C5") (pin "2") (pinfunction "2_2") (pintype "passive"))
      (node (ref "J3") (pin "VBUS") (pinfunction "VBUS_VBUS") (pintype "bidirectional"))
      (node (ref "SJ1") (pin "1") (pinfunction "1_1") (pintype "passive"))
      (node (ref "U2") (pin "5") (pinfunction "VCC_5") (pintype "power_in"))
      (node (ref "U5") (pin "3") (pinfunction "UVCC_3") (pintype "power_in"))
      (node (ref "U5") (pin "8") (pinfunction "VBUS_8") (pintype "bidirectional"))
    )
    (net (code "39") (name "/X-DIR") (class "Default")
      (node (ref "P1") (pin "DIR") (pinfunction "DIR_DIR") (pintype "bidirectional"))
      (node (ref "U5") (pin "50") (pinfunction "PA1_AD1_50") (pintype "bidirectional"))
    )
    (net (code "40") (name "/X-STEP") (class "Default")
      (node (ref "P1") (pin "STEP") (pinfunction "STEP_STEP") (pintype "bidirectional"))
      (node (ref "U5") (pin "49") (pinfunction "PA2_AD2_49") (pintype "bidirectional"))
    )
    (net (code "41") (name "/X-STOP") (class "Default")
      (node (ref "JP8") (pin "1") (pinfunction "1_1") (pintype "passive"))
      (node (ref "U5") (pin "16") (pinfunction "PB6_PCINT6_OC1B_16") (pintype "bidirectional"))
    )
    (net (code "42") (name "/XTAL1") (class "Default")
      (node (ref "C13") (pin "2") (pinfunction "2_2") (pintype "passive"))
      (node (ref "U5") (pin "24") (pinfunction "XTAL1_24") (pintype "passive"))
      (node (ref "X1") (pin "P$2") (pinfunction "2_P$2") (pintype "passive"))
    )
    (net (code "43") (name "/XTAL2") (class "Default")
      (node (ref "C12") (pin "2") (pinfunction "2_2") (pintype "passive"))
      (node (ref "U5") (pin "23") (pinfunction "XTAL2_23") (pintype "passive"))
      (node (ref "X1") (pin "P$1") (pinfunction "1_P$1") (pintype "passive"))
    )
    (net (code "44") (name "/Y-DIR") (class "Default")
      (node (ref "P2") (pin "DIR") (pinfunction "DIR_DIR") (pintype "bidirectional"))
      (node (ref "U5") (pin "47") (pinfunction "PA4_AD4_47") (pintype "bidirectional"))
    )
    (net (code "45") (name "/Y-STEP") (class "Default")
      (node (ref "P2") (pin "STEP") (pinfunction "STEP_STEP") (pintype "bidirectional"))
      (node (ref "U5") (pin "46") (pinfunction "PA5_AD5_46") (pintype "bidirectional"))
    )
    (net (code "46") (name "/Y-STOP") (class "Default")
      (node (ref "JP9") (pin "1") (pinfunction "1_1") (pintype "passive"))
      (node (ref "U5") (pin "15") (pinfunction "PB5_PCINT5_OC1A_15") (pintype "bidirectional"))
    )
    (net (code "47") (name "/Z-DIR") (class "Default")
      (node (ref "P3") (pin "DIR") (pinfunction "DIR_DIR") (pintype "bidirectional"))
      (node (ref "U5") (pin "44") (pinfunction "PA7_AD7_44") (pintype "bidirectional"))
    )
    (net (code "48") (name "/Z-STEP") (class "Default")
      (node (ref "P3") (pin "STEP") (pinfunction "STEP_STEP") (pintype "bidirectional"))
      (node (ref "U5") (pin "42") (pinfunction "PC7_A15_IC3_CLK0_42") (pintype "bidirectional"))
    )
    (net (code "49") (name "/Z-STOP") (class "Default")
      (node (ref "Q5") (pin "2") (pinfunction "E_2") (pintype "passive"))
      (node (ref "U5") (pin "1") (pinfunction "PE6_INT6_AIN0_1") (pintype "bidirectional"))
    )
    (net (code "50") (name "/~{E1-ENABLE}") (class "Default")
      (node (ref "P4") (pin "!EN") (pinfunction "~{ENABLE}_!EN") (pintype "input"))
      (node (ref "R22") (pin "2") (pinfunction "2_2") (pintype "passive"))
      (node (ref "U5") (pin "38") (pinfunction "PC3_A11_T3_38") (pintype "bidirectional"))
    )
    (net (code "51") (name "/~{E2-ENABLE}") (class "Default")
      (node (ref "P5") (pin "!EN") (pinfunction "~{ENABLE}_!EN") (pintype "input"))
      (node (ref "R23") (pin "2") (pinfunction "2_2") (pintype "passive"))
      (node (ref "U5") (pin "35") (pinfunction "PC0_A8_35") (pintype "bidirectional"))
    )
    (net (code "52") (name "/~{HOTBED}") (class "Default")
      (node (ref "R10") (pin "1") (pinfunction "1_1") (pintype "passive"))
      (node (ref "R11") (pin "1") (pinfunction "1_1") (pintype "passive"))
      (node (ref "U5") (pin "39") (pinfunction "PC4_A12_OC3C_39") (pintype "bidirectional"))
    )
    (net (code "53") (name "/~{HOTEND-1}") (class "Default")
      (node (ref "R8") (pin "1") (pinfunction "1_1") (pintype "passive"))
      (node (ref "R9") (pin "1") (pinfunction "1_1") (pintype "passive"))
      (node (ref "U5") (pin "40") (pinfunction "PC5_A13_OC3B_40") (pintype "bidirectional"))
    )
    (net (code "54") (name "/~{HOTEND-2}") (class "Default")
      (node (ref "R14") (pin "1") (pinfunction "1_1") (pintype "passive"))
      (node (ref "R15") (pin "1") (pinfunction "1_1") (pintype "passive"))
      (node (ref "U5") (pin "58") (pinfunction "PF3_ADC3_58") (pintype "bidirectional"))
    )
    (net (code "55") (name "/~{PWM-FAN}") (class "Default")
      (node (ref "R2") (pin "1") (pinfunction "1_1") (pintype "passive"))
      (node (ref "R3") (pin "1") (pinfunction "1_1") (pintype "passive"))
      (node (ref "U5") (pin "41") (pinfunction "PC6_A14_OC3A_41") (pintype "bidirectional"))
    )
    (net (code "56") (name "/~{RESET}") (class "Default")
      (node (ref "JP5") (pin "2") (pinfunction "2_2") (pintype "passive"))
      (node (ref "R12") (pin "1") (pinfunction "1_1") (pintype "passive"))
      (node (ref "S1") (pin "3") (pinfunction "3_3") (pintype "passive"))
      (node (ref "S1") (pin "4") (pinfunction "4_4") (pintype "passive"))
      (node (ref "U5") (pin "20") (pinfunction "/RESET_20") (pintype "bidirectional"))
    )
    (net (code "57") (name "/~{X-ENABLE}") (class "Default")
      (node (ref "P1") (pin "!EN") (pinfunction "~{ENABLE}_!EN") (pintype "input"))
      (node (ref "R20") (pin "2") (pinfunction "2_2") (pintype "passive"))
      (node (ref "U5") (pin "51") (pinfunction "PA0_AD0_51") (pintype "bidirectional"))
    )
    (net (code "58") (name "/~{Y-ENABLE}") (class "Default")
      (node (ref "P2") (pin "!EN") (pinfunction "~{ENABLE}_!EN") (pintype "input"))
      (node (ref "R19") (pin "2") (pinfunction "2_2") (pintype "passive"))
      (node (ref "U5") (pin "48") (pinfunction "PA3_AD3_48") (pintype "bidirectional"))
    )
    (net (code "59") (name "/~{Z-ENABLE}") (class "Default")
      (node (ref "P3") (pin "!EN") (pinfunction "~{ENABLE}_!EN") (pintype "input"))
      (node (ref "R21") (pin "2") (pinfunction "2_2") (pintype "passive"))
      (node (ref "U5") (pin "45") (pinfunction "PA6_AD6_45") (pintype "bidirectional"))
    )
    (net (code "60") (name "5V") (class "Default")
      (node (ref "C10") (pin "1") (pinfunction "1_1") (pintype "passive"))
      (node (ref "C3") (pin "1") (pinfunction "1_1") (pintype "passive"))
      (node (ref "C6") (pin "2") (pinfunction "2_2") (pintype "passive"))
      (node (ref "C7") (pin "2") (pinfunction "2_2") (pintype "passive"))
      (node (ref "C8") (pin "1") (pinfunction "1_1") (pintype "passive"))
      (node (ref "J8") (pin "2") (pinfunction "2_2") (pintype "passive"))
      (node (ref "JP4") (pin "3") (pinfunction "3_3") (pintype "passive"))
      (node (ref "JP5") (pin "5") (pinfunction "5_5") (pintype "passive"))
      (node (ref "JP6") (pin "3") (pinfunction "3_3") (pintype "passive"))
      (node (ref "L1") (pin "2") (pinfunction "2_2") (pintype "passive"))
      (node (ref "P1") (pin "VDD") (pinfunction "VDD_VDD") (pintype "power_in"))
      (node (ref "P2") (pin "VDD") (pinfunction "VDD_VDD") (pintype "power_in"))
      (node (ref "P3") (pin "VDD") (pinfunction "VDD_VDD") (pintype "power_in"))
      (node (ref "P4") (pin "VDD") (pinfunction "VDD_VDD") (pintype "power_in"))
      (node (ref "P5") (pin "VDD") (pinfunction "VDD_VDD") (pintype "power_in"))
      (node (ref "R1") (pin "2") (pinfunction "2_2") (pintype "passive"))
      (node (ref "R12") (pin "2") (pinfunction "2_2") (pintype "passive"))
      (node (ref "R13") (pin "2") (pinfunction "2_2") (pintype "passive"))
      (node (ref "R16") (pin "2") (pinfunction "2_2") (pintype "passive"))
      (node (ref "R17") (pin "2") (pinfunction "2_2") (pintype "passive"))
      (node (ref "R18") (pin "2") (pinfunction "2_2") (pintype "passive"))
      (node (ref "R19") (pin "1") (pinfunction "1_1") (pintype "passive"))
      (node (ref "R20") (pin "1") (pinfunction "1_1") (pintype "passive"))
      (node (ref "R21") (pin "1") (pinfunction "1_1") (pintype "passive"))
      (node (ref "R22") (pin "1") (pinfunction "1_1") (pintype "passive"))
      (node (ref "R23") (pin "1") (pinfunction "1_1") (pintype "passive"))
      (node (ref "R4") (pin "1") (pinfunction "1_1") (pintype "passive"))
      (node (ref "SJ1") (pin "2") (pinfunction "2_2") (pintype "passive"))
      (node (ref "SJ10") (pin "2") (pinfunction "2_2") (pintype "passive"))
      (node (ref "SJ11") (pin "2") (pinfunction "2_2") (pintype "passive"))
      (node (ref "SJ12") (pin "2") (pinfunction "2_2") (pintype "passive"))
      (node (ref "SJ13") (pin "2") (pinfunction "2_2") (pintype "passive"))
      (node (ref "SJ14") (pin "2") (pinfunction "2_2") (pintype "passive"))
      (node (ref "SJ15") (pin "2") (pinfunction "2_2") (pintype "passive"))
      (node (ref "SJ16") (pin "2") (pinfunction "2_2") (pintype "passive"))
      (node (ref "SJ2") (pin "2") (pinfunction "2_2") (pintype "passive"))
      (node (ref "SJ3") (pin "2") (pinfunction "2_2") (pintype "passive"))
      (node (ref "SJ4") (pin "2") (pinfunction "2_2") (pintype "passive"))
      (node (ref "SJ5") (pin "2") (pinfunction "2_2") (pintype "passive"))
      (node (ref "SJ6") (pin "2") (pinfunction "2_2") (pintype "passive"))
      (node (ref "SJ7") (pin "2") (pinfunction "2_2") (pintype "passive"))
      (node (ref "SJ8") (pin "2") (pinfunction "2_2") (pintype "passive"))
      (node (ref "SJ9") (pin "2") (pinfunction "2_2") (pintype "passive"))
      (node (ref "U3") (pin "1") (pinfunction "IN_1") (pintype "power_in"))
      (node (ref "U4") (pin "14") (pinfunction "VCCB_14") (pintype "power_in"))
      (node (ref "U5") (pin "21") (pinfunction "VCC_21") (pintype "power_in"))
      (node (ref "U5") (pin "52") (pinfunction "VCC_52") (pintype "power_in"))
      (node (ref "U5") (pin "62") (pinfunction "AREF_62") (pintype "power_in"))
      (node (ref "U5") (pin "64") (pinfunction "AVCC_64") (pintype "power_in"))
    )
    (net (code "61") (name "12V") (class "Default")
      (node (ref "C1") (pin "1") (pinfunction "1_1") (pintype "passive"))
      (node (ref "C17") (pin "+") (pinfunction "+_+") (pintype "passive"))
      (node (ref "C18") (pin "+") (pinfunction "+_+") (pintype "passive"))
      (node (ref "C19") (pin "+") (pinfunction "+_+") (pintype "passive"))
      (node (ref "C2") (pin "+") (pinfunction "+_+") (pintype "passive"))
      (node (ref "C20") (pin "+") (pinfunction "+_+") (pintype "passive"))
      (node (ref "C21") (pin "+") (pinfunction "+_+") (pintype "passive"))
      (node (ref "J1") (pin "1") (pinfunction "1_1") (pintype "passive"))
      (node (ref "J10") (pin "3") (pinfunction "3_3") (pintype "power_in"))
      (node (ref "J10") (pin "4") (pinfunction "4_4") (pintype "power_in"))
      (node (ref "J4") (pin "1") (pinfunction "1_1") (pintype "passive"))
      (node (ref "J5") (pin "1") (pinfunction "1_1") (pintype "power_in"))
      (node (ref "J5") (pin "2") (pinfunction "2_2") (pintype "power_in"))
      (node (ref "J6") (pin "1") (pinfunction "S_1") (pintype "passive"))
      (node (ref "J6") (pin "2") (pinfunction "S_2") (pintype "passive"))
      (node (ref "J6") (pin "3") (pinfunction "S_3") (pintype "passive"))
      (node (ref "J7") (pin "3") (pinfunction "3_3") (pintype "power_in"))
      (node (ref "J7") (pin "4") (pinfunction "4_4") (pintype "power_in"))
      (node (ref "J8") (pin "3") (pinfunction "3_3") (pintype "passive"))
      (node (ref "J9") (pin "3") (pinfunction "3_3") (pintype "power_in"))
      (node (ref "J9") (pin "4") (pinfunction "4_4") (pintype "power_in"))
      (node (ref "JP4") (pin "1") (pinfunction "1_1") (pintype "passive"))
      (node (ref "JP6") (pin "1") (pinfunction "1_1") (pintype "passive"))
      (node (ref "P1") (pin "VMOT") (pinfunction "VMOT_VMOT") (pintype "power_in"))
      (node (ref "P2") (pin "VMOT") (pinfunction "VMOT_VMOT") (pintype "power_in"))
      (node (ref "P3") (pin "VMOT") (pinfunction "VMOT_VMOT") (pintype "power_in"))
      (node (ref "P4") (pin "VMOT") (pinfunction "VMOT_VMOT") (pintype "power_in"))
      (node (ref "P5") (pin "VMOT") (pinfunction "VMOT_VMOT") (pintype "power_in"))
      (node (ref "U1") (pin "4") (pinfunction "~{SHDN}_4") (pintype "input"))
      (node (ref "U1") (pin "5") (pinfunction "VIN_5") (pintype "power_in"))
    )
    (net (code "62") (name "GND") (class "Default")
      (node (ref "C1") (pin "2") (pinfunction "2_2") (pintype "passive"))
      (node (ref "C10") (pin "2") (pinfunction "2_2") (pintype "passive"))
      (node (ref "C11") (pin "2") (pinfunction "2_2") (pintype "passive"))
      (node (ref "C12") (pin "1") (pinfunction "1_1") (pintype "passive"))
      (node (ref "C13") (pin "1") (pinfunction "1_1") (pintype "passive"))
      (node (ref "C14") (pin "1") (pinfunction "1_1") (pintype "passive"))
      (node (ref "C15") (pin "1") (pinfunction "1_1") (pintype "passive"))
      (node (ref "C16") (pin "1") (pinfunction "1_1") (pintype "passive"))
      (node (ref "C17") (pin "-") (pinfunction "-_-") (pintype "passive"))
      (node (ref "C18") (pin "-") (pinfunction "-_-") (pintype "passive"))
      (node (ref "C19") (pin "-") (pinfunction "-_-") (pintype "passive"))
      (node (ref "C2") (pin "-") (pinfunction "-_-") (pintype "passive"))
      (node (ref "C20") (pin "-") (pinfunction "-_-") (pintype "passive"))
      (node (ref "C21") (pin "-") (pinfunction "-_-") (pintype "passive"))
      (node (ref "C3") (pin "2") (pinfunction "2_2") (pintype "passive"))
      (node (ref "C5") (pin "1") (pinfunction "1_1") (pintype "passive"))
      (node (ref "C6") (pin "1") (pinfunction "1_1") (pintype "passive"))
      (node (ref "C7") (pin "1") (pinfunction "1_1") (pintype "passive"))
      (node (ref "C8") (pin "2") (pinfunction "2_2") (pintype "passive"))
      (node (ref "C9") (pin "1") (pinfunction "1_1") (pintype "passive"))
      (node (ref "D1") (pin "A") (pinfunction "A_A") (pintype "passive"))
      (node (ref "D2") (pin "A") (pinfunction "A_A") (pintype "passive"))
      (node (ref "J1") (pin "2") (pinfunction "2_2") (pintype "passive"))
      (node (ref "J11") (pin "2") (pinfunction "2_2") (pintype "passive"))
      (node (ref "J12") (pin "2") (pinfunction "2_2") (pintype "passive"))
      (node (ref "J13") (pin "2") (pinfunction "2_2") (pintype "passive"))
      (node (ref "J2") (pin "6") (pinfunction "GND_6") (pintype "power_in"))
      (node (ref "J2") (pin "C1") (pinfunction "SHEILD_C1") (pintype "bidirectional"))
      (node (ref "J2") (pin "C2") (pinfunction "SHIELD_C2") (pintype "bidirectional"))
      (node (ref "J2") (pin "C3") (pinfunction "SHIELD_C3") (pintype "bidirectional"))
      (node (ref "J2") (pin "C4") (pinfunction "SHIELD_C4") (pintype "bidirectional"))
      (node (ref "J2") (pin "CD1") (pinfunction "CD1_CD1") (pintype "bidirectional"))
      (node (ref "J3") (pin "GND") (pinfunction "GND_GND") (pintype "bidirectional"))
      (node (ref "J3") (pin "GND1") (pinfunction "GND_GND1") (pintype "bidirectional"))
      (node (ref "J3") (pin "GND2") (pinfunction "GND_GND2") (pintype "bidirectional"))
      (node (ref "J3") (pin "GND3") (pinfunction "GND_GND3") (pintype "bidirectional"))
      (node (ref "J3") (pin "GND4") (pinfunction "GND_GND4") (pintype "bidirectional"))
      (node (ref "J3") (pin "GND5") (pinfunction "GND_GND5") (pintype "bidirectional"))
      (node (ref "J3") (pin "GND6") (pinfunction "GND_GND6") (pintype "bidirectional"))
      (node (ref "J3") (pin "GND7") (pinfunction "GND_GND7") (pintype "bidirectional"))
      (node (ref "J3") (pin "GND8") (pinfunction "GND_GND8") (pintype "bidirectional"))
      (node (ref "J5") (pin "3") (pinfunction "3_3") (pintype "power_in"))
      (node (ref "J5") (pin "4") (pinfunction "4_4") (pintype "power_in"))
      (node (ref "J6") (pin "4") (pinfunction "S_4") (pintype "passive"))
      (node (ref "J6") (pin "5") (pinfunction "S_5") (pintype "passive"))
      (node (ref "J6") (pin "6") (pinfunction "S_6") (pintype "passive"))
      (node (ref "J8") (pin "1") (pinfunction "1_1") (pintype "passive"))
      (node (ref "JP10") (pin "3") (pinfunction "3_3") (pintype "passive"))
      (node (ref "JP3") (pin "2") (pinfunction "2_2") (pintype "passive"))
      (node (ref "JP5") (pin "1") (pinfunction "1_1") (pintype "passive"))
      (node (ref "JP7") (pin "3") (pinfunction "3_3") (pintype "passive"))
      (node (ref "JP8") (pin "3") (pinfunction "3_3") (pintype "passive"))
      (node (ref "JP9") (pin "3") (pinfunction "3_3") (pintype "passive"))
      (node (ref "LED1") (pin "C") (pinfunction "C_C") (pintype "passive"))
      (node (ref "P1") (pin "GNDMOT") (pinfunction "GNDMOT_GNDMOT") (pintype "power_in"))
      (node (ref "P1") (pin "GNDVDD") (pinfunction "GNDVDD_GNDVDD") (pintype "power_in"))
      (node (ref "P2") (pin "GNDMOT") (pinfunction "GNDMOT_GNDMOT") (pintype "power_in"))
      (node (ref "P2") (pin "GNDVDD") (pinfunction "GNDVDD_GNDVDD") (pintype "power_in"))
      (node (ref "P3") (pin "GNDMOT") (pinfunction "GNDMOT_GNDMOT") (pintype "power_in"))
      (node (ref "P3") (pin "GNDVDD") (pinfunction "GNDVDD_GNDVDD") (pintype "power_in"))
      (node (ref "P4") (pin "GNDMOT") (pinfunction "GNDMOT_GNDMOT") (pintype "power_in"))
      (node (ref "P4") (pin "GNDVDD") (pinfunction "GNDVDD_GNDVDD") (pintype "power_in"))
      (node (ref "P5") (pin "GNDMOT") (pinfunction "GNDMOT_GNDMOT") (pintype "power_in"))
      (node (ref "P5") (pin "GNDVDD") (pinfunction "GNDVDD_GNDVDD") (pintype "power_in"))
      (node (ref "Q1") (pin "2") (pinfunction "S_2") (pintype "passive"))
      (node (ref "Q2") (pin "1") (pinfunction "S1_1") (pintype "passive"))
      (node (ref "Q2") (pin "2") (pinfunction "S2_2") (pintype "passive"))
      (node (ref "Q2") (pin "3") (pinfunction "S3_3") (pintype "passive"))
      (node (ref "Q3") (pin "1") (pinfunction "S1_1") (pintype "passive"))
      (node (ref "Q3") (pin "2") (pinfunction "S2_2") (pintype "passive"))
      (node (ref "Q3") (pin "3") (pinfunction "S3_3") (pintype "passive"))
      (node (ref "Q4") (pin "1") (pinfunction "S1_1") (pintype "passive"))
      (node (ref "Q4") (pin "2") (pinfunction "S2_2") (pintype "passive"))
      (node (ref "Q4") (pin "3") (pinfunction "S3_3") (pintype "passive"))
      (node (ref "Q5") (pin "3") (pinfunction "C_3") (pintype "passive"))
      (node (ref "R10") (pin "2") (pinfunction "2_2") (pintype "passive"))
      (node (ref "R14") (pin "2") (pinfunction "2_2") (pintype "passive"))
      (node (ref "R2") (pin "2") (pinfunction "2_2") (pintype "passive"))
      (node (ref "R5") (pin "2") (pinfunction "2_2") (pintype "passive"))
      (node (ref "R8") (pin "2") (pinfunction "2_2") (pintype "passive"))
      (node (ref "S1") (pin "1") (pinfunction "1_1") (pintype "passive"))
      (node (ref "S1") (pin "2") (pinfunction "2_2") (pintype "passive"))
      (node (ref "SCREW1") (pin "GND") (pinfunction "P$1_GND") (pintype "bidirectional"))
      (node (ref "SCREW2") (pin "GND") (pinfunction "P$1_GND") (pintype "bidirectional"))
      (node (ref "SCREW3") (pin "GND") (pinfunction "P$1_GND") (pintype "bidirectional"))
      (node (ref "SCREW4") (pin "GND") (pinfunction "P$1_GND") (pintype "bidirectional"))
      (node (ref "U1") (pin "2") (pinfunction "GND_2") (pintype "power_in"))
      (node (ref "U2") (pin "2") (pinfunction "GND_2") (pintype "power_in"))
      (node (ref "U3") (pin "3") (pinfunction "GND_3") (pintype "power_in"))
      (node (ref "U4") (pin "7") (pinfunction "GND_7") (pintype "power_in"))
      (node (ref "U5") (pin "22") (pinfunction "GND_22") (pintype "power_in"))
      (node (ref "U5") (pin "53") (pinfunction "GND_53") (pintype "power_in"))
      (node (ref "U5") (pin "6") (pinfunction "UGND_6") (pintype "power_in"))
      (node (ref "U5") (pin "63") (pinfunction "AGND_63") (pintype "power_in"))
    )
    (net (code "63") (name "Net-(F1-PadP$2)") (class "Default")
      (node (ref "F1") (pin "P$2") (pinfunction "P$2_P$2") (pintype "passive"))
      (node (ref "J4") (pin "2") (pinfunction "2_2") (pintype "passive"))
    )
    (net (code "64") (name "Net-(JP6-Pad2)") (class "Default")
      (node (ref "JP6") (pin "2") (pinfunction "2_2") (pintype "passive"))
      (node (ref "JP7") (pin "2") (pinfunction "2_2") (pintype "passive"))
    )
    (net (code "65") (name "Net-(JP10-Pad2)") (class "Default")
      (node (ref "JP10") (pin "2") (pinfunction "2_2") (pintype "passive"))
      (node (ref "JP4") (pin "2") (pinfunction "2_2") (pintype "passive"))
      (node (ref "JP8") (pin "2") (pinfunction "2_2") (pintype "passive"))
      (node (ref "JP9") (pin "2") (pinfunction "2_2") (pintype "passive"))
    )
    (net (code "66") (name "Net-(LED1-PadA)") (class "Default")
      (node (ref "LED1") (pin "A") (pinfunction "A_A") (pintype "passive"))
      (node (ref "R1") (pin "1") (pinfunction "1_1") (pintype "passive"))
    )
    (net (code "67") (name "Net-(P1-MOT-1A)") (class "Default")
      (node (ref "JP11") (pin "2") (pinfunction "2_2") (pintype "passive"))
      (node (ref "P1") (pin "1A") (pinfunction "MOT-1A_1A") (pintype "power_in"))
    )
    (net (code "68") (name "Net-(P1-MOT-1B)") (class "Default")
      (node (ref "JP11") (pin "1") (pinfunction "1_1") (pintype "passive"))
      (node (ref "P1") (pin "1B") (pinfunction "MOT-1B_1B") (pintype "power_in"))
    )
    (net (code "69") (name "Net-(P1-MOT-2A)") (class "Default")
      (node (ref "JP11") (pin "3") (pinfunction "3_3") (pintype "passive"))
      (node (ref "P1") (pin "2A") (pinfunction "MOT-2A_2A") (pintype "power_in"))
    )
    (net (code "70") (name "Net-(P1-MOT-2B)") (class "Default")
      (node (ref "JP11") (pin "4") (pinfunction "4_4") (pintype "passive"))
      (node (ref "P1") (pin "2B") (pinfunction "MOT-2B_2B") (pintype "power_in"))
    )
    (net (code "71") (name "Net-(P1-PadMS1)") (class "Default")
      (node (ref "P1") (pin "MS1") (pinfunction "MS1_MS1") (pintype "input"))
      (node (ref "SJ12") (pin "1") (pinfunction "1_1") (pintype "passive"))
    )
    (net (code "72") (name "Net-(P1-PadMS2)") (class "Default")
      (node (ref "P1") (pin "MS2") (pinfunction "MS2_MS2") (pintype "input"))
      (node (ref "SJ7") (pin "1") (pinfunction "1_1") (pintype "passive"))
    )
    (net (code "73") (name "Net-(P1-PadMS3)") (class "Default")
      (node (ref "P1") (pin "MS3") (pinfunction "MS3_MS3") (pintype "input"))
      (node (ref "SJ2") (pin "1") (pinfunction "1_1") (pintype "passive"))
    )
    (net (code "74") (name "Net-(P1-~{RESET})") (class "Default")
      (node (ref "P1") (pin "!RST") (pinfunction "~{RESET}_!RST") (pintype "input"))
      (node (ref "P1") (pin "!SLP") (pinfunction "~{SLEEP}_!SLP") (pintype "input"))
    )
    (net (code "75") (name "Net-(P2-MOT-1A)") (class "Default")
      (node (ref "JP12") (pin "2") (pinfunction "2_2") (pintype "passive"))
      (node (ref "P2") (pin "1A") (pinfunction "MOT-1A_1A") (pintype "power_in"))
    )
    (net (code "76") (name "Net-(P2-MOT-1B)") (class "Default")
      (node (ref "JP12") (pin "1") (pinfunction "1_1") (pintype "passive"))
      (node (ref "P2") (pin "1B") (pinfunction "MOT-1B_1B") (pintype "power_in"))
    )
    (net (code "77") (name "Net-(P2-MOT-2A)") (class "Default")
      (node (ref "JP12") (pin "3") (pinfunction "3_3") (pintype "passive"))
      (node (ref "P2") (pin "2A") (pinfunction "MOT-2A_2A") (pintype "power_in"))
    )
    (net (code "78") (name "Net-(P2-MOT-2B)") (class "Default")
      (node (ref "JP12") (pin "4") (pinfunction "4_4") (pintype "passive"))
      (node (ref "P2") (pin "2B") (pinfunction "MOT-2B_2B") (pintype "power_in"))
    )
    (net (code "79") (name "Net-(P2-PadMS1)") (class "Default")
      (node (ref "P2") (pin "MS1") (pinfunction "MS1_MS1") (pintype "input"))
      (node (ref "SJ13") (pin "1") (pinfunction "1_1") (pintype "passive"))
    )
    (net (code "80") (name "Net-(P2-PadMS2)") (class "Default")
      (node (ref "P2") (pin "MS2") (pinfunction "MS2_MS2") (pintype "input"))
      (node (ref "SJ8") (pin "1") (pinfunction "1_1") (pintype "passive"))
    )
    (net (code "81") (name "Net-(P2-PadMS3)") (class "Default")
      (node (ref "P2") (pin "MS3") (pinfunction "MS3_MS3") (pintype "input"))
      (node (ref "SJ3") (pin "1") (pinfunction "1_1") (pintype "passive"))
    )
    (net (code "82") (name "Net-(P2-~{RESET})") (class "Default")
      (node (ref "P2") (pin "!RST") (pinfunction "~{RESET}_!RST") (pintype "input"))
      (node (ref "P2") (pin "!SLP") (pinfunction "~{SLEEP}_!SLP") (pintype "input"))
    )
    (net (code "83") (name "Net-(P3-MOT-1A)") (class "Default")
      (node (ref "JP15") (pin "2") (pinfunction "2_2") (pintype "passive"))
      (node (ref "P3") (pin "1A") (pinfunction "MOT-1A_1A") (pintype "power_in"))
    )
    (net (code "84") (name "Net-(P3-MOT-1B)") (class "Default")
      (node (ref "JP15") (pin "1") (pinfunction "1_1") (pintype "passive"))
      (node (ref "P3") (pin "1B") (pinfunction "MOT-1B_1B") (pintype "power_in"))
    )
    (net (code "85") (name "Net-(P3-MOT-2A)") (class "Default")
      (node (ref "JP15") (pin "3") (pinfunction "3_3") (pintype "passive"))
      (node (ref "P3") (pin "2A") (pinfunction "MOT-2A_2A") (pintype "power_in"))
    )
    (net (code "86") (name "Net-(P3-MOT-2B)") (class "Default")
      (node (ref "JP15") (pin "4") (pinfunction "4_4") (pintype "passive"))
      (node (ref "P3") (pin "2B") (pinfunction "MOT-2B_2B") (pintype "power_in"))
    )
    (net (code "87") (name "Net-(P3-PadMS1)") (class "Default")
      (node (ref "P3") (pin "MS1") (pinfunction "MS1_MS1") (pintype "input"))
      (node (ref "SJ14") (pin "1") (pinfunction "1_1") (pintype "passive"))
    )
    (net (code "88") (name "Net-(P3-PadMS2)") (class "Default")
      (node (ref "P3") (pin "MS2") (pinfunction "MS2_MS2") (pintype "input"))
      (node (ref "SJ9") (pin "1") (pinfunction "1_1") (pintype "passive"))
    )
    (net (code "89") (name "Net-(P3-PadMS3)") (class "Default")
      (node (ref "P3") (pin "MS3") (pinfunction "MS3_MS3") (pintype "input"))
      (node (ref "SJ4") (pin "1") (pinfunction "1_1") (pintype "passive"))
    )
    (net (code "90") (name "Net-(P3-~{RESET})") (class "Default")
      (node (ref "P3") (pin "!RST") (pinfunction "~{RESET}_!RST") (pintype "input"))
      (node (ref "P3") (pin "!SLP") (pinfunction "~{SLEEP}_!SLP") (pintype "input"))
    )
    (net (code "91") (name "Net-(P4-MOT-1A)") (class "Default")
      (node (ref "JP13") (pin "2") (pinfunction "2_2") (pintype "passive"))
      (node (ref "P4") (pin "1A") (pinfunction "MOT-1A_1A") (pintype "power_in"))
    )
    (net (code "92") (name "Net-(P4-MOT-1B)") (class "Default")
      (node (ref "JP13") (pin "1") (pinfunction "1_1") (pintype "passive"))
      (node (ref "P4") (pin "1B") (pinfunction "MOT-1B_1B") (pintype "power_in"))
    )
    (net (code "93") (name "Net-(P4-MOT-2A)") (class "Default")
      (node (ref "JP13") (pin "3") (pinfunction "3_3") (pintype "passive"))
      (node (ref "P4") (pin "2A") (pinfunction "MOT-2A_2A") (pintype "power_in"))
    )
    (net (code "94") (name "Net-(P4-MOT-2B)") (class "Default")
      (node (ref "JP13") (pin "4") (pinfunction "4_4") (pintype "passive"))
      (node (ref "P4") (pin "2B") (pinfunction "MOT-2B_2B") (pintype "power_in"))
    )
    (net (code "95") (name "Net-(P4-PadMS1)") (class "Default")
      (node (ref "P4") (pin "MS1") (pinfunction "MS1_MS1") (pintype "input"))
      (node (ref "SJ15") (pin "1") (pinfunction "1_1") (pintype "passive"))
    )
    (net (code "96") (name "Net-(P4-PadMS2)") (class "Default")
      (node (ref "P4") (pin "MS2") (pinfunction "MS2_MS2") (pintype "input"))
      (node (ref "SJ10") (pin "1") (pinfunction "1_1") (pintype "passive"))
    )
    (net (code "97") (name "Net-(P4-PadMS3)") (class "Default")
      (node (ref "P4") (pin "MS3") (pinfunction "MS3_MS3") (pintype "input"))
      (node (ref "SJ5") (pin "1") (pinfunction "1_1") (pintype "passive"))
    )
    (net (code "98") (name "Net-(P4-~{RESET})") (class "Default")
      (node (ref "P4") (pin "!RST") (pinfunction "~{RESET}_!RST") (pintype "input"))
      (node (ref "P4") (pin "!SLP") (pinfunction "~{SLEEP}_!SLP") (pintype "input"))
    )
    (net (code "99") (name "Net-(P5-MOT-1A)") (class "Default")
      (node (ref "JP14") (pin "2") (pinfunction "2_2") (pintype "passive"))
      (node (ref "P5") (pin "1A") (pinfunction "MOT-1A_1A") (pintype "power_in"))
    )
    (net (code "100") (name "Net-(P5-MOT-1B)") (class "Default")
      (node (ref "JP14") (pin "1") (pinfunction "1_1") (pintype "passive"))
      (node (ref "P5") (pin "1B") (pinfunction "MOT-1B_1B") (pintype "power_in"))
    )
    (net (code "101") (name "Net-(P5-MOT-2A)") (class "Default")
      (node (ref "JP14") (pin "3") (pinfunction "3_3") (pintype "passive"))
      (node (ref "P5") (pin "2A") (pinfunction "MOT-2A_2A") (pintype "power_in"))
    )
    (net (code "102") (name "Net-(P5-MOT-2B)") (class "Default")
      (node (ref "JP14") (pin "4") (pinfunction "4_4") (pintype "passive"))
      (node (ref "P5") (pin "2B") (pinfunction "MOT-2B_2B") (pintype "power_in"))
    )
    (net (code "103") (name "Net-(P5-PadMS1)") (class "Default")
      (node (ref "P5") (pin "MS1") (pinfunction "MS1_MS1") (pintype "input"))
      (node (ref "SJ16") (pin "1") (pinfunction "1_1") (pintype "passive"))
    )
    (net (code "104") (name "Net-(P5-PadMS2)") (class "Default")
      (node (ref "P5") (pin "MS2") (pinfunction "MS2_MS2") (pintype "input"))
      (node (ref "SJ11") (pin "1") (pinfunction "1_1") (pintype "passive"))
    )
    (net (code "105") (name "Net-(P5-PadMS3)") (class "Default")
      (node (ref "P5") (pin "MS3") (pinfunction "MS3_MS3") (pintype "input"))
      (node (ref "SJ6") (pin "1") (pinfunction "1_1") (pintype "passive"))
    )
    (net (code "106") (name "Net-(P5-~{RESET})") (class "Default")
      (node (ref "P5") (pin "!RST") (pinfunction "~{RESET}_!RST") (pintype "input"))
      (node (ref "P5") (pin "!SLP") (pinfunction "~{SLEEP}_!SLP") (pintype "input"))
    )
    (net (code "107") (name "Net-(Q1-D)") (class "Default")
      (node (ref "D2") (pin "C") (pinfunction "C_C") (pintype "passive"))
      (node (ref "F1") (pin "P$1") (pinfunction "P$1_P$1") (pintype "passive"))
      (node (ref "Q1") (pin "3") (pinfunction "D_3") (pintype "passive"))
    )
    (net (code "108") (name "Net-(Q1-G)") (class "Default")
      (node (ref "Q1") (pin "1") (pinfunction "G_1") (pintype "passive"))
      (node (ref "R3") (pin "2") (pinfunction "2_2") (pintype "passive"))
    )
    (net (code "109") (name "Net-(Q2-D)") (class "Default")
      (node (ref "J7") (pin "1") (pinfunction "1_1") (pintype "power_in"))
      (node (ref "J7") (pin "2") (pinfunction "2_2") (pintype "power_in"))
      (node (ref "Q2") (pin "5-8") (pinfunction "D_5-8") (pintype "passive"))
    )
    (net (code "110") (name "Net-(Q2-G)") (class "Default")
      (node (ref "Q2") (pin "4") (pinfunction "G_4") (pintype "passive"))
      (node (ref "R9") (pin "2") (pinfunction "2_2") (pintype "passive"))
    )
    (net (code "111") (name "Net-(Q3-D)") (class "Default")
      (node (ref "J9") (pin "1") (pinfunction "1_1") (pintype "power_in"))
      (node (ref "J9") (pin "2") (pinfunction "2_2") (pintype "power_in"))
      (node (ref "Q3") (pin "5-8") (pinfunction "D_5-8") (pintype "passive"))
    )
    (net (code "112") (name "Net-(Q3-G)") (class "Default")
      (node (ref "Q3") (pin "4") (pinfunction "G_4") (pintype "passive"))
      (node (ref "R11") (pin "2") (pinfunction "2_2") (pintype "passive"))
    )
    (net (code "113") (name "Net-(Q4-D)") (class "Default")
      (node (ref "J10") (pin "1") (pinfunction "1_1") (pintype "power_in"))
      (node (ref "J10") (pin "2") (pinfunction "2_2") (pintype "power_in"))
      (node (ref "Q4") (pin "5-8") (pinfunction "D_5-8") (pintype "passive"))
    )
    (net (code "114") (name "Net-(Q4-G)") (class "Default")
      (node (ref "Q4") (pin "4") (pinfunction "G_4") (pintype "passive"))
      (node (ref "R15") (pin "2") (pinfunction "2_2") (pintype "passive"))
    )
    (net (code "115") (name "Net-(Q5-B)") (class "Default")
      (node (ref "JP7") (pin "1") (pinfunction "1_1") (pintype "passive"))
      (node (ref "Q5") (pin "1") (pinfunction "B_1") (pintype "passive"))
    )
    (net (code "116") (name "Net-(U1-CB)") (class "Default")
      (node (ref "C4") (pin "2") (pinfunction "2_2") (pintype "passive"))
      (node (ref "U1") (pin "1") (pinfunction "CB_1") (pintype "passive"))
    )
    (net (code "117") (name "Net-(U1-FB)") (class "Default")
      (node (ref "R4") (pin "2") (pinfunction "2_2") (pintype "passive"))
      (node (ref "R5") (pin "1") (pinfunction "1_1") (pintype "passive"))
      (node (ref "U1") (pin "3") (pinfunction "FB_3") (pintype "passive"))
    )
    (net (code "118") (name "Net-(U1-SW)") (class "Default")
      (node (ref "C4") (pin "1") (pinfunction "1_1") (pintype "passive"))
      (node (ref "D1") (pin "C") (pinfunction "C_C") (pintype "passive"))
      (node (ref "L1") (pin "1") (pinfunction "1_1") (pintype "passive"))
      (node (ref "U1") (pin "6") (pinfunction "SW_6") (pintype "passive"))
    )
    (net (code "119") (name "Net-(U5-D+)") (class "Default")
      (node (ref "R7") (pin "2") (pinfunction "2_2") (pintype "passive"))
      (node (ref "U5") (pin "5") (pinfunction "D+_5") (pintype "bidirectional"))
    )
    (net (code "120") (name "Net-(U5-D-)") (class "Default")
      (node (ref "R6") (pin "2") (pinfunction "2_2") (pintype "passive"))
      (node (ref "U5") (pin "4") (pinfunction "D-_4") (pintype "bidirectional"))
    )
    (net (code "121") (name "Net-(U5-UCAP)") (class "Default")
      (node (ref "C9") (pin "2") (pinfunction "2_2") (pintype "passive"))
      (node (ref "U5") (pin "7") (pinfunction "UCAP_7") (pintype "power_in"))
    )
    (net (code "122") (name "unconnected-(J2-DAT1-Pad8)") (class "Default")
      (node (ref "J2") (pin "8") (pinfunction "DAT1_8") (pintype "bidirectional"))
    )
    (net (code "123") (name "unconnected-(J2-DAT2-Pad1)") (class "Default")
      (node (ref "J2") (pin "1") (pinfunction "DAT2_1") (pintype "bidirectional"))
    )
    (net (code "124") (name "unconnected-(U2-IO3-Pad4)") (class "Default")
      (node (ref "U2") (pin "4") (pinfunction "IO3_4") (pintype "bidirectional"))
    )
    (net (code "125") (name "unconnected-(U2-IO4-Pad6)") (class "Default")
      (node (ref "U2") (pin "6") (pinfunction "IO4_6") (pintype "bidirectional"))
    )
  )
)
